# 614_donkey_sch.net
KiCad netlist of a schematic drawn in EAGLE
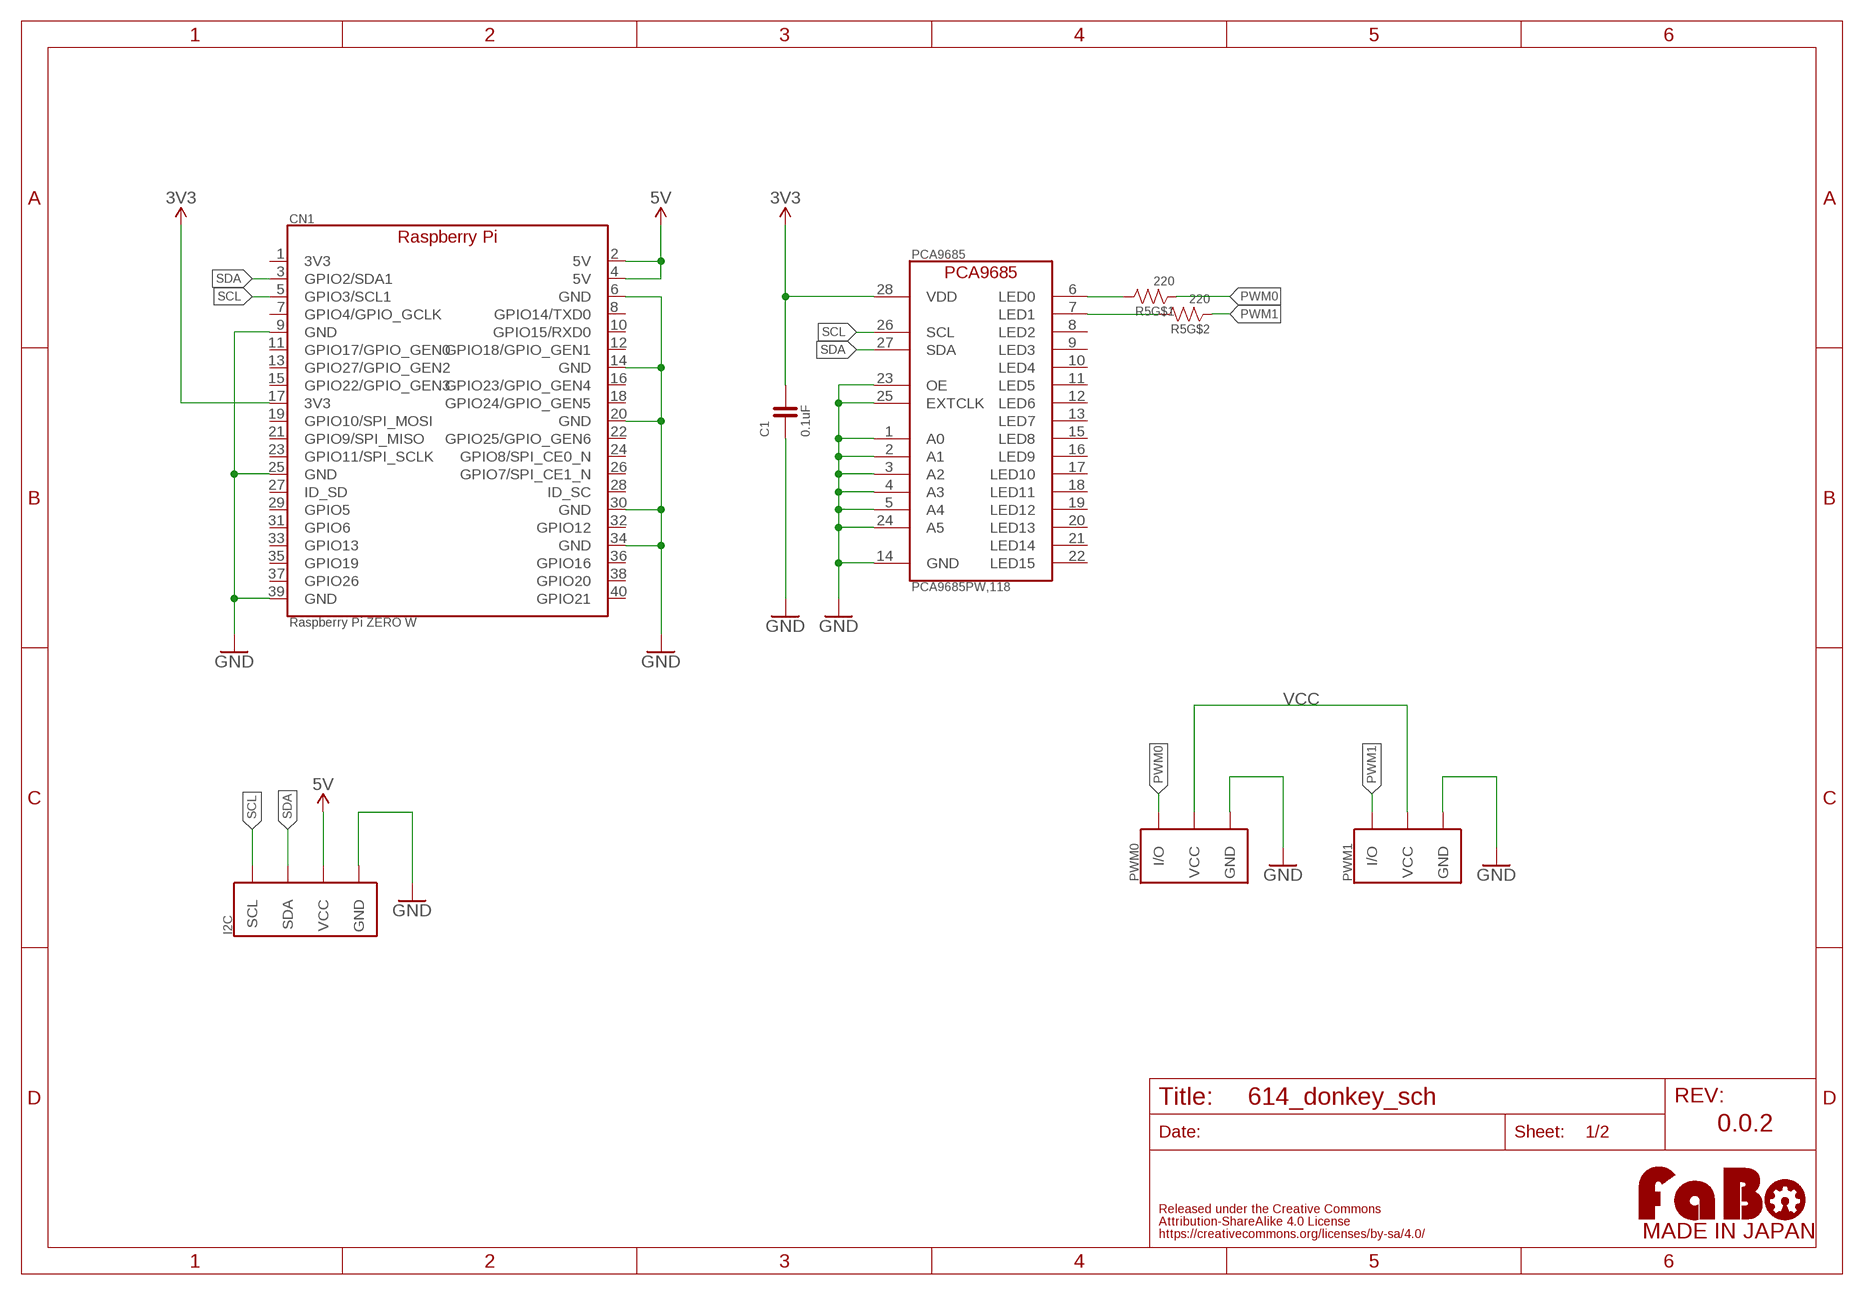
[diagram p0: schematic, sheet 1]
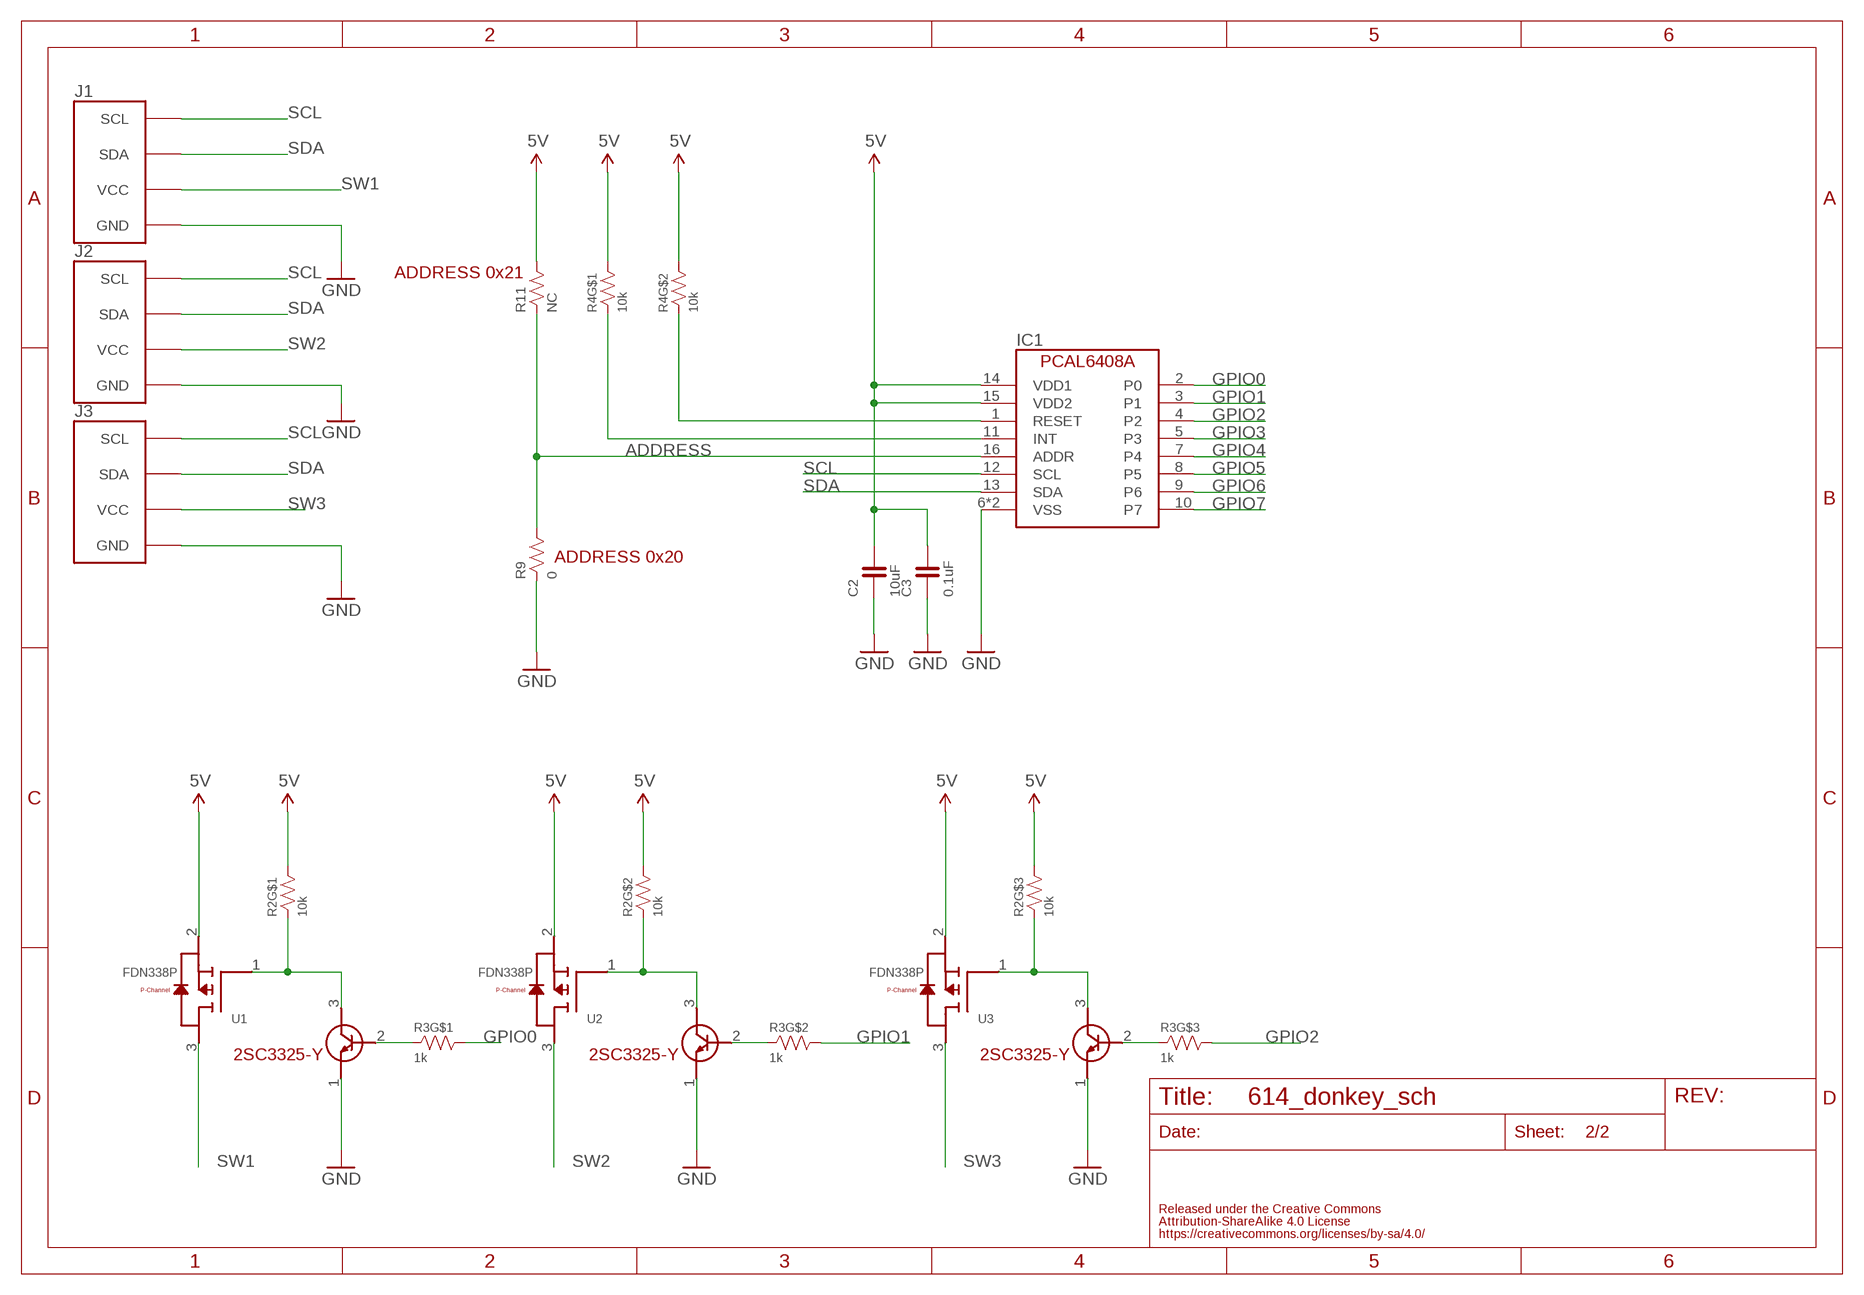
[diagram p1: schematic, sheet 2]

(export (version "E")
  (design (tool "Eeschema 10.0.6"))
  (components
    (comp (ref "C2")
      (value "10uF")
      (footprint "eagle-import:0603")
      (libsource (lib "eagle-import") (part "CAPACITOR-0603"))
    )
    (comp (ref "C3")
      (value "0.1uF")
      (footprint "eagle-import:0603")
      (libsource (lib "eagle-import") (part "CAPACITOR-0603"))
    )
    (comp (ref "IC1")
      (value "NX-PCAL6408A")
      (footprint "eagle-import:NXP-PCAL6408A")
      (libsource (lib "eagle-import") (part "NX-PCAL6408A"))
    )
    (comp (ref "J1")
      (value "FABO_BRICK_I2C-S04B-PASK-2")
      (footprint "eagle-import:FABO_BRICK_I2C_S04B-PASK-2")
      (libsource (lib "eagle-import") (part "FABO_BRICK_I2C-S04B-PASK-2"))
    )
    (comp (ref "J2")
      (value "FABO_BRICK_I2C-S04B-PASK-2")
      (footprint "eagle-import:FABO_BRICK_I2C_S04B-PASK-2")
      (libsource (lib "eagle-import") (part "FABO_BRICK_I2C-S04B-PASK-2"))
    )
    (comp (ref "J3")
      (value "FABO_BRICK_I2C-S04B-PASK-2")
      (footprint "eagle-import:FABO_BRICK_I2C_S04B-PASK-2")
      (libsource (lib "eagle-import") (part "FABO_BRICK_I2C-S04B-PASK-2"))
    )
    (comp (ref "R2")
      (value "10k")
      (footprint "eagle-import:EXBV8V")
      (libsource (lib "eagle-import") (part "RESISTOR_ARRAY"))
    )
    (comp (ref "R3")
      (value "1k")
      (footprint "eagle-import:EXBV8V")
      (libsource (lib "eagle-import") (part "RESISTOR_ARRAY"))
    )
    (comp (ref "R4")
      (value "10k")
      (footprint "eagle-import:EXBV8V")
      (libsource (lib "eagle-import") (part "RESISTOR_ARRAY"))
    )
    (comp (ref "R9")
      (value "0")
      (footprint "eagle-import:0603-NARROW")
      (libsource (lib "eagle-import") (part "RESISTOR-0603-NARROW"))
    )
    (comp (ref "R11")
      (value "NC")
      (footprint "eagle-import:0603-NARROW")
      (libsource (lib "eagle-import") (part "RESISTOR-0603-NARROW"))
    )
    (comp (ref "T1")
      (value "2SC3325-Y")
      (footprint "eagle-import:SC-59")
      (libsource (lib "eagle-import") (part "2SC3325-Y"))
    )
    (comp (ref "T2")
      (value "2SC3325-Y")
      (footprint "eagle-import:SC-59")
      (libsource (lib "eagle-import") (part "2SC3325-Y"))
    )
    (comp (ref "T3")
      (value "2SC3325-Y")
      (footprint "eagle-import:SC-59")
      (libsource (lib "eagle-import") (part "2SC3325-Y"))
    )
    (comp (ref "U1")
      (value "FDN338P")
      (footprint "eagle-import:SOT-23")
      (libsource (lib "eagle-import") (part "FDN338P"))
    )
    (comp (ref "U2")
      (value "FDN338P")
      (footprint "eagle-import:SOT-23")
      (libsource (lib "eagle-import") (part "FDN338P"))
    )
    (comp (ref "U3")
      (value "FDN338P")
      (footprint "eagle-import:SOT-23")
      (libsource (lib "eagle-import") (part "FDN338P"))
    )
    (comp (ref "C1")
      (value "0.1uF")
      (footprint "eagle-import:EIA0603")
      (libsource (lib "eagle-import") (part "component_CAPACITOR-0603"))
    )
    (comp (ref "CN1")
      (value "Raspberry Pi ZERO W")
      (footprint "eagle-import:PIN_2X20_NARROW")
      (libsource (lib "eagle-import") (part "RASPBERRY_CON"))
    )
    (comp (ref "I2C")
      (value "FABO-BRICK-I2C_SIDE_SMD_BOSS")
      (footprint "eagle-import:SM04B-PASS-1")
      (libsource (lib "eagle-import") (part "FABO-BRICK-I2C_SIDE_SMD_BOSS"))
    )
    (comp (ref "LOGO1")
      (value "LOGO_FABO-M")
      (footprint "eagle-import:LOGO_FABO_M")
      (libsource (lib "eagle-import") (part "LOGO_FABO-M"))
    )
    (comp (ref "PCA9685")
      (value "PCA9685PW,118")
      (footprint "eagle-import:TSSOP-28")
      (libsource (lib "eagle-import") (part "PCA9685PW"))
    )
    (comp (ref "PWM0")
      (value "FABO-BRICK-3PIN_HEADER")
      (footprint "eagle-import:PIN_1X3_NARROW")
      (libsource (lib "eagle-import") (part "FABO-BRICK-3PIN_HEADER"))
    )
    (comp (ref "PWM1")
      (value "FABO-BRICK-3PIN_HEADER")
      (footprint "eagle-import:PIN_1X3_NARROW")
      (libsource (lib "eagle-import") (part "FABO-BRICK-3PIN_HEADER"))
    )
    (comp (ref "R5")
      (value "220")
      (footprint "eagle-import:EXBV8V")
      (libsource (lib "eagle-import") (part "RESISTOR_ARRAY"))
    )
  )
  (nets
    (net (code "1") (name "3V3") (class "Default")
      (node (ref "C1") (pin "2") (pinfunction "2_2") (pintype "passive"))
      (node (ref "CN1") (pin "17") (pinfunction "3V3_17") (pintype "bidirectional"))
      (node (ref "PCA9685") (pin "28") (pinfunction "VDD_28") (pintype "bidirectional"))
    )
    (net (code "2") (name "5V") (class "Default")
      (node (ref "C2") (pin "2") (pinfunction "2_2") (pintype "passive"))
      (node (ref "C3") (pin "2") (pinfunction "2_2") (pintype "passive"))
      (node (ref "CN1") (pin "2") (pinfunction "5V_2") (pintype "bidirectional"))
      (node (ref "CN1") (pin "4") (pinfunction "5V_4") (pintype "bidirectional"))
      (node (ref "I2C") (pin "3") (pinfunction "VCC_3") (pintype "bidirectional"))
      (node (ref "IC1") (pin "14") (pinfunction "VDD1_14") (pintype "bidirectional"))
      (node (ref "IC1") (pin "15") (pinfunction "VDD2_15") (pintype "bidirectional"))
      (node (ref "R11") (pin "2") (pinfunction "2_2") (pintype "bidirectional"))
      (node (ref "R2") (pin "6") (pinfunction "2_6") (pintype "bidirectional"))
      (node (ref "R2") (pin "7") (pinfunction "2_7") (pintype "bidirectional"))
      (node (ref "R2") (pin "8") (pinfunction "2_8") (pintype "bidirectional"))
      (node (ref "R4") (pin "7") (pinfunction "2_7") (pintype "bidirectional"))
      (node (ref "R4") (pin "8") (pinfunction "2_8") (pintype "bidirectional"))
      (node (ref "U1") (pin "2") (pinfunction "S_2") (pintype "passive"))
      (node (ref "U2") (pin "2") (pinfunction "S_2") (pintype "passive"))
      (node (ref "U3") (pin "2") (pinfunction "S_2") (pintype "passive"))
    )
    (net (code "3") (name "ADDRESS") (class "Default")
      (node (ref "IC1") (pin "16") (pinfunction "ADDR_16") (pintype "bidirectional"))
      (node (ref "R11") (pin "1") (pinfunction "1_1") (pintype "bidirectional"))
      (node (ref "R9") (pin "2") (pinfunction "2_2") (pintype "bidirectional"))
    )
    (net (code "4") (name "GND") (class "Default")
      (node (ref "C1") (pin "1") (pinfunction "1_1") (pintype "passive"))
      (node (ref "C2") (pin "1") (pinfunction "1_1") (pintype "passive"))
      (node (ref "C3") (pin "1") (pinfunction "1_1") (pintype "passive"))
      (node (ref "CN1") (pin "14") (pinfunction "GND_14") (pintype "bidirectional"))
      (node (ref "CN1") (pin "20") (pinfunction "GND_20") (pintype "bidirectional"))
      (node (ref "CN1") (pin "25") (pinfunction "GND_25") (pintype "bidirectional"))
      (node (ref "CN1") (pin "30") (pinfunction "GND_30") (pintype "bidirectional"))
      (node (ref "CN1") (pin "34") (pinfunction "GND_34") (pintype "bidirectional"))
      (node (ref "CN1") (pin "39") (pinfunction "GND_39") (pintype "bidirectional"))
      (node (ref "CN1") (pin "6") (pinfunction "GND_6") (pintype "bidirectional"))
      (node (ref "CN1") (pin "9") (pinfunction "GND_9") (pintype "bidirectional"))
      (node (ref "I2C") (pin "4") (pinfunction "GND_4") (pintype "bidirectional"))
      (node (ref "IC1") (pin "17") (pinfunction "VSS_17") (pintype "bidirectional"))
      (node (ref "IC1") (pin "6") (pinfunction "VSS_6") (pintype "bidirectional"))
      (node (ref "J1") (pin "GND") (pinfunction "GND_GND") (pintype "bidirectional"))
      (node (ref "J2") (pin "GND") (pinfunction "GND_GND") (pintype "bidirectional"))
      (node (ref "J3") (pin "GND") (pinfunction "GND_GND") (pintype "bidirectional"))
      (node (ref "PCA9685") (pin "1") (pinfunction "A0_1") (pintype "bidirectional"))
      (node (ref "PCA9685") (pin "14") (pinfunction "GND_14") (pintype "bidirectional"))
      (node (ref "PCA9685") (pin "2") (pinfunction "A1_2") (pintype "bidirectional"))
      (node (ref "PCA9685") (pin "23") (pinfunction "OE_23") (pintype "bidirectional"))
      (node (ref "PCA9685") (pin "24") (pinfunction "A5_24") (pintype "bidirectional"))
      (node (ref "PCA9685") (pin "25") (pinfunction "EXTCLK_25") (pintype "bidirectional"))
      (node (ref "PCA9685") (pin "3") (pinfunction "A2_3") (pintype "bidirectional"))
      (node (ref "PCA9685") (pin "4") (pinfunction "A3_4") (pintype "bidirectional"))
      (node (ref "PCA9685") (pin "5") (pinfunction "A4_5") (pintype "bidirectional"))
      (node (ref "PWM0") (pin "3") (pinfunction "GND_3") (pintype "bidirectional"))
      (node (ref "PWM1") (pin "3") (pinfunction "GND_3") (pintype "bidirectional"))
      (node (ref "R9") (pin "1") (pinfunction "1_1") (pintype "bidirectional"))
      (node (ref "T1") (pin "1") (pinfunction "E_1") (pintype "bidirectional"))
      (node (ref "T2") (pin "1") (pinfunction "E_1") (pintype "bidirectional"))
      (node (ref "T3") (pin "1") (pinfunction "E_1") (pintype "bidirectional"))
    )
    (net (code "5") (name "GPIO0") (class "Default")
      (node (ref "IC1") (pin "2") (pinfunction "P0_2") (pintype "bidirectional"))
      (node (ref "R3") (pin "8") (pinfunction "2_8") (pintype "bidirectional"))
    )
    (net (code "6") (name "GPIO1") (class "Default")
      (node (ref "IC1") (pin "3") (pinfunction "P1_3") (pintype "bidirectional"))
      (node (ref "R3") (pin "7") (pinfunction "2_7") (pintype "bidirectional"))
    )
    (net (code "7") (name "GPIO2") (class "Default")
      (node (ref "IC1") (pin "4") (pinfunction "P2_4") (pintype "bidirectional"))
      (node (ref "R3") (pin "6") (pinfunction "2_6") (pintype "bidirectional"))
    )
    (net (code "8") (name "GPIO3") (class "Default")
      (node (ref "IC1") (pin "5") (pinfunction "P3_5") (pintype "bidirectional"))
    )
    (net (code "9") (name "GPIO4") (class "Default")
      (node (ref "IC1") (pin "7") (pinfunction "P4_7") (pintype "bidirectional"))
    )
    (net (code "10") (name "GPIO5") (class "Default")
      (node (ref "IC1") (pin "8") (pinfunction "P5_8") (pintype "bidirectional"))
    )
    (net (code "11") (name "GPIO6") (class "Default")
      (node (ref "IC1") (pin "9") (pinfunction "P6_9") (pintype "bidirectional"))
    )
    (net (code "12") (name "GPIO7") (class "Default")
      (node (ref "IC1") (pin "10") (pinfunction "P7_10") (pintype "bidirectional"))
    )
    (net (code "13") (name "Net-(IC1-INT)") (class "Default")
      (node (ref "IC1") (pin "11") (pinfunction "INT_11") (pintype "bidirectional"))
      (node (ref "R4") (pin "1") (pinfunction "1_1") (pintype "bidirectional"))
    )
    (net (code "14") (name "Net-(IC1-RESET)") (class "Default")
      (node (ref "IC1") (pin "1") (pinfunction "RESET_1") (pintype "bidirectional"))
      (node (ref "R4") (pin "2") (pinfunction "1_2") (pintype "bidirectional"))
    )
    (net (code "15") (name "Net-(PCA9685-LED0)") (class "Default")
      (node (ref "PCA9685") (pin "6") (pinfunction "LED0_6") (pintype "bidirectional"))
      (node (ref "R5") (pin "8") (pinfunction "2_8") (pintype "bidirectional"))
    )
    (net (code "16") (name "Net-(PCA9685-LED1)") (class "Default")
      (node (ref "PCA9685") (pin "7") (pinfunction "LED1_7") (pintype "bidirectional"))
      (node (ref "R5") (pin "7") (pinfunction "2_7") (pintype "bidirectional"))
    )
    (net (code "17") (name "Net-(R2B-1)") (class "Default")
      (node (ref "R2") (pin "2") (pinfunction "1_2") (pintype "bidirectional"))
      (node (ref "T2") (pin "3") (pinfunction "C_3") (pintype "bidirectional"))
      (node (ref "U2") (pin "1") (pinfunction "G_1") (pintype "passive"))
    )
    (net (code "18") (name "Net-(R2C-1)") (class "Default")
      (node (ref "R2") (pin "3") (pinfunction "1_3") (pintype "bidirectional"))
      (node (ref "T3") (pin "3") (pinfunction "C_3") (pintype "bidirectional"))
      (node (ref "U3") (pin "1") (pinfunction "G_1") (pintype "passive"))
    )
    (net (code "19") (name "Net-(R3B-1)") (class "Default")
      (node (ref "R3") (pin "2") (pinfunction "1_2") (pintype "bidirectional"))
      (node (ref "T2") (pin "2") (pinfunction "B_2") (pintype "bidirectional"))
    )
    (net (code "20") (name "Net-(R3C-1)") (class "Default")
      (node (ref "R3") (pin "3") (pinfunction "1_3") (pintype "bidirectional"))
      (node (ref "T3") (pin "2") (pinfunction "B_2") (pintype "bidirectional"))
    )
    (net (code "21") (name "Net-(T1-B)") (class "Default")
      (node (ref "R3") (pin "1") (pinfunction "1_1") (pintype "bidirectional"))
      (node (ref "T1") (pin "2") (pinfunction "B_2") (pintype "bidirectional"))
    )
    (net (code "22") (name "Net-(T1-C)") (class "Default")
      (node (ref "R2") (pin "1") (pinfunction "1_1") (pintype "bidirectional"))
      (node (ref "T1") (pin "3") (pinfunction "C_3") (pintype "bidirectional"))
      (node (ref "U1") (pin "1") (pinfunction "G_1") (pintype "passive"))
    )
    (net (code "23") (name "PWM0") (class "Default")
      (node (ref "PWM0") (pin "1") (pinfunction "I/O_1") (pintype "bidirectional"))
      (node (ref "R5") (pin "1") (pinfunction "1_1") (pintype "bidirectional"))
    )
    (net (code "24") (name "PWM1") (class "Default")
      (node (ref "PWM1") (pin "1") (pinfunction "I/O_1") (pintype "bidirectional"))
      (node (ref "R5") (pin "2") (pinfunction "1_2") (pintype "bidirectional"))
    )
    (net (code "25") (name "SCL") (class "Default")
      (node (ref "CN1") (pin "5") (pinfunction "GPIO3/SCL1_5") (pintype "bidirectional"))
      (node (ref "I2C") (pin "1") (pinfunction "SCL_1") (pintype "bidirectional"))
      (node (ref "IC1") (pin "12") (pinfunction "SCL_12") (pintype "bidirectional"))
      (node (ref "J1") (pin "SCL") (pinfunction "SCL_SCL") (pintype "bidirectional"))
      (node (ref "J2") (pin "SCL") (pinfunction "SCL_SCL") (pintype "bidirectional"))
      (node (ref "J3") (pin "SCL") (pinfunction "SCL_SCL") (pintype "bidirectional"))
      (node (ref "PCA9685") (pin "26") (pinfunction "SCL_26") (pintype "bidirectional"))
    )
    (net (code "26") (name "SDA") (class "Default")
      (node (ref "CN1") (pin "3") (pinfunction "GPIO2/SDA1_3") (pintype "bidirectional"))
      (node (ref "I2C") (pin "2") (pinfunction "SDA_2") (pintype "bidirectional"))
      (node (ref "IC1") (pin "13") (pinfunction "SDA_13") (pintype "bidirectional"))
      (node (ref "J1") (pin "SDA") (pinfunction "SDA_SDA") (pintype "bidirectional"))
      (node (ref "J2") (pin "SDA") (pinfunction "SDA_SDA") (pintype "bidirectional"))
      (node (ref "J3") (pin "SDA") (pinfunction "SDA_SDA") (pintype "bidirectional"))
      (node (ref "PCA9685") (pin "27") (pinfunction "SDA_27") (pintype "bidirectional"))
    )
    (net (code "27") (name "SW1") (class "Default")
      (node (ref "J1") (pin "VCC") (pinfunction "VCC_VCC") (pintype "bidirectional"))
      (node (ref "U1") (pin "3") (pinfunction "D_3") (pintype "passive"))
    )
    (net (code "28") (name "SW2") (class "Default")
      (node (ref "J2") (pin "VCC") (pinfunction "VCC_VCC") (pintype "bidirectional"))
      (node (ref "U2") (pin "3") (pinfunction "D_3") (pintype "passive"))
    )
    (net (code "29") (name "SW3") (class "Default")
      (node (ref "J3") (pin "VCC") (pinfunction "VCC_VCC") (pintype "bidirectional"))
      (node (ref "U3") (pin "3") (pinfunction "D_3") (pintype "passive"))
    )
    (net (code "30") (name "VCC") (class "Default")
      (node (ref "PWM0") (pin "2") (pinfunction "VCC_2") (pintype "bidirectional"))
      (node (ref "PWM1") (pin "2") (pinfunction "VCC_2") (pintype "bidirectional"))
    )
    (net (code "31") (name "unconnected-(CN1-3V3-Pad1)") (class "Default")
      (node (ref "CN1") (pin "1") (pinfunction "3V3_1") (pintype "bidirectional"))
    )
    (net (code "32") (name "unconnected-(CN1-GPIO4{slash}GPIO_GCLK-Pad7)") (class "Default")
      (node (ref "CN1") (pin "7") (pinfunction "GPIO4/GPIO_GCLK_7") (pintype "bidirectional"))
    )
    (net (code "33") (name "unconnected-(CN1-GPIO5-Pad29)") (class "Default")
      (node (ref "CN1") (pin "29") (pinfunction "GPIO5_29") (pintype "bidirectional"))
    )
    (net (code "34") (name "unconnected-(CN1-GPIO6-Pad31)") (class "Default")
      (node (ref "CN1") (pin "31") (pinfunction "GPIO6_31") (pintype "bidirectional"))
    )
    (net (code "35") (name "unconnected-(CN1-GPIO7{slash}SPI_CE1_N-Pad26)") (class "Default")
      (node (ref "CN1") (pin "26") (pinfunction "GPIO7/SPI_CE1_N_26") (pintype "bidirectional"))
    )
    (net (code "36") (name "unconnected-(CN1-GPIO8{slash}SPI_CE0_N-Pad24)") (class "Default")
      (node (ref "CN1") (pin "24") (pinfunction "GPIO8/SPI_CE0_N_24") (pintype "bidirectional"))
    )
    (net (code "37") (name "unconnected-(CN1-GPIO9{slash}SPI_MISO-Pad21)") (class "Default")
      (node (ref "CN1") (pin "21") (pinfunction "GPIO9/SPI_MISO_21") (pintype "bidirectional"))
    )
    (net (code "38") (name "unconnected-(CN1-GPIO10{slash}SPI_MOSI-Pad19)") (class "Default")
      (node (ref "CN1") (pin "19") (pinfunction "GPIO10/SPI_MOSI_19") (pintype "bidirectional"))
    )
    (net (code "39") (name "unconnected-(CN1-GPIO11{slash}SPI_SCLK-Pad23)") (class "Default")
      (node (ref "CN1") (pin "23") (pinfunction "GPIO11/SPI_SCLK_23") (pintype "bidirectional"))
    )
    (net (code "40") (name "unconnected-(CN1-GPIO12-Pad32)") (class "Default")
      (node (ref "CN1") (pin "32") (pinfunction "GPIO12_32") (pintype "bidirectional"))
    )
    (net (code "41") (name "unconnected-(CN1-GPIO13-Pad33)") (class "Default")
      (node (ref "CN1") (pin "33") (pinfunction "GPIO13_33") (pintype "bidirectional"))
    )
    (net (code "42") (name "unconnected-(CN1-GPIO14{slash}TXD0-Pad8)") (class "Default")
      (node (ref "CN1") (pin "8") (pinfunction "GPIO14/TXD0_8") (pintype "bidirectional"))
    )
    (net (code "43") (name "unconnected-(CN1-GPIO15{slash}RXD0-Pad10)") (class "Default")
      (node (ref "CN1") (pin "10") (pinfunction "GPIO15/RXD0_10") (pintype "bidirectional"))
    )
    (net (code "44") (name "unconnected-(CN1-GPIO16-Pad36)") (class "Default")
      (node (ref "CN1") (pin "36") (pinfunction "GPIO16_36") (pintype "bidirectional"))
    )
    (net (code "45") (name "unconnected-(CN1-GPIO17{slash}GPIO_GEN0-Pad11)") (class "Default")
      (node (ref "CN1") (pin "11") (pinfunction "GPIO17/GPIO_GEN0_11") (pintype "bidirectional"))
    )
    (net (code "46") (name "unconnected-(CN1-GPIO18{slash}GPIO_GEN1-Pad12)") (class "Default")
      (node (ref "CN1") (pin "12") (pinfunction "GPIO18/GPIO_GEN1_12") (pintype "bidirectional"))
    )
    (net (code "47") (name "unconnected-(CN1-GPIO19-Pad35)") (class "Default")
      (node (ref "CN1") (pin "35") (pinfunction "GPIO19_35") (pintype "bidirectional"))
    )
    (net (code "48") (name "unconnected-(CN1-GPIO20-Pad38)") (class "Default")
      (node (ref "CN1") (pin "38") (pinfunction "GPIO20_38") (pintype "bidirectional"))
    )
    (net (code "49") (name "unconnected-(CN1-GPIO21-Pad40)") (class "Default")
      (node (ref "CN1") (pin "40") (pinfunction "GPIO21_40") (pintype "bidirectional"))
    )
    (net (code "50") (name "unconnected-(CN1-GPIO22{slash}GPIO_GEN3-Pad15)") (class "Default")
      (node (ref "CN1") (pin "15") (pinfunction "GPIO22/GPIO_GEN3_15") (pintype "bidirectional"))
    )
    (net (code "51") (name "unconnected-(CN1-GPIO23{slash}GPIO_GEN4-Pad16)") (class "Default")
      (node (ref "CN1") (pin "16") (pinfunction "GPIO23/GPIO_GEN4_16") (pintype "bidirectional"))
    )
    (net (code "52") (name "unconnected-(CN1-GPIO24{slash}GPIO_GEN5-Pad18)") (class "Default")
      (node (ref "CN1") (pin "18") (pinfunction "GPIO24/GPIO_GEN5_18") (pintype "bidirectional"))
    )
    (net (code "53") (name "unconnected-(CN1-GPIO25{slash}GPIO_GEN6-Pad22)") (class "Default")
      (node (ref "CN1") (pin "22") (pinfunction "GPIO25/GPIO_GEN6_22") (pintype "bidirectional"))
    )
    (net (code "54") (name "unconnected-(CN1-GPIO26-Pad37)") (class "Default")
      (node (ref "CN1") (pin "37") (pinfunction "GPIO26_37") (pintype "bidirectional"))
    )
    (net (code "55") (name "unconnected-(CN1-GPIO27{slash}GPIO_GEN2-Pad13)") (class "Default")
      (node (ref "CN1") (pin "13") (pinfunction "GPIO27/GPIO_GEN2_13") (pintype "bidirectional"))
    )
    (net (code "56") (name "unconnected-(CN1-ID_SC-Pad28)") (class "Default")
      (node (ref "CN1") (pin "28") (pinfunction "ID_SC_28") (pintype "bidirectional"))
    )
    (net (code "57") (name "unconnected-(CN1-ID_SD-Pad27)") (class "Default")
      (node (ref "CN1") (pin "27") (pinfunction "ID_SD_27") (pintype "bidirectional"))
    )
    (net (code "58") (name "unconnected-(PCA9685-LED2-Pad8)") (class "Default")
      (node (ref "PCA9685") (pin "8") (pinfunction "LED2_8") (pintype "bidirectional"))
    )
    (net (code "59") (name "unconnected-(PCA9685-LED3-Pad9)") (class "Default")
      (node (ref "PCA9685") (pin "9") (pinfunction "LED3_9") (pintype "bidirectional"))
    )
    (net (code "60") (name "unconnected-(PCA9685-LED4-Pad10)") (class "Default")
      (node (ref "PCA9685") (pin "10") (pinfunction "LED4_10") (pintype "bidirectional"))
    )
    (net (code "61") (name "unconnected-(PCA9685-LED5-Pad11)") (class "Default")
      (node (ref "PCA9685") (pin "11") (pinfunction "LED5_11") (pintype "bidirectional"))
    )
    (net (code "62") (name "unconnected-(PCA9685-LED6-Pad12)") (class "Default")
      (node (ref "PCA9685") (pin "12") (pinfunction "LED6_12") (pintype "bidirectional"))
    )
    (net (code "63") (name "unconnected-(PCA9685-LED7-Pad13)") (class "Default")
      (node (ref "PCA9685") (pin "13") (pinfunction "LED7_13") (pintype "bidirectional"))
    )
    (net (code "64") (name "unconnected-(PCA9685-LED8-Pad15)") (class "Default")
      (node (ref "PCA9685") (pin "15") (pinfunction "LED8_15") (pintype "bidirectional"))
    )
    (net (code "65") (name "unconnected-(PCA9685-LED9-Pad16)") (class "Default")
      (node (ref "PCA9685") (pin "16") (pinfunction "LED9_16") (pintype "bidirectional"))
    )
    (net (code "66") (name "unconnected-(PCA9685-LED10-Pad17)") (class "Default")
      (node (ref "PCA9685") (pin "17") (pinfunction "LED10_17") (pintype "bidirectional"))
    )
    (net (code "67") (name "unconnected-(PCA9685-LED11-Pad18)") (class "Default")
      (node (ref "PCA9685") (pin "18") (pinfunction "LED11_18") (pintype "bidirectional"))
    )
    (net (code "68") (name "unconnected-(PCA9685-LED12-Pad19)") (class "Default")
      (node (ref "PCA9685") (pin "19") (pinfunction "LED12_19") (pintype "bidirectional"))
    )
    (net (code "69") (name "unconnected-(PCA9685-LED13-Pad20)") (class "Default")
      (node (ref "PCA9685") (pin "20") (pinfunction "LED13_20") (pintype "bidirectional"))
    )
    (net (code "70") (name "unconnected-(PCA9685-LED14-Pad21)") (class "Default")
      (node (ref "PCA9685") (pin "21") (pinfunction "LED14_21") (pintype "bidirectional"))
    )
    (net (code "71") (name "unconnected-(PCA9685-LED15-Pad22)") (class "Default")
      (node (ref "PCA9685") (pin "22") (pinfunction "LED15_22") (pintype "bidirectional"))
    )
  )
)
